# Tractive_System_Active_Light_rev3.net
KiCad netlist of a schematic drawn in EAGLE
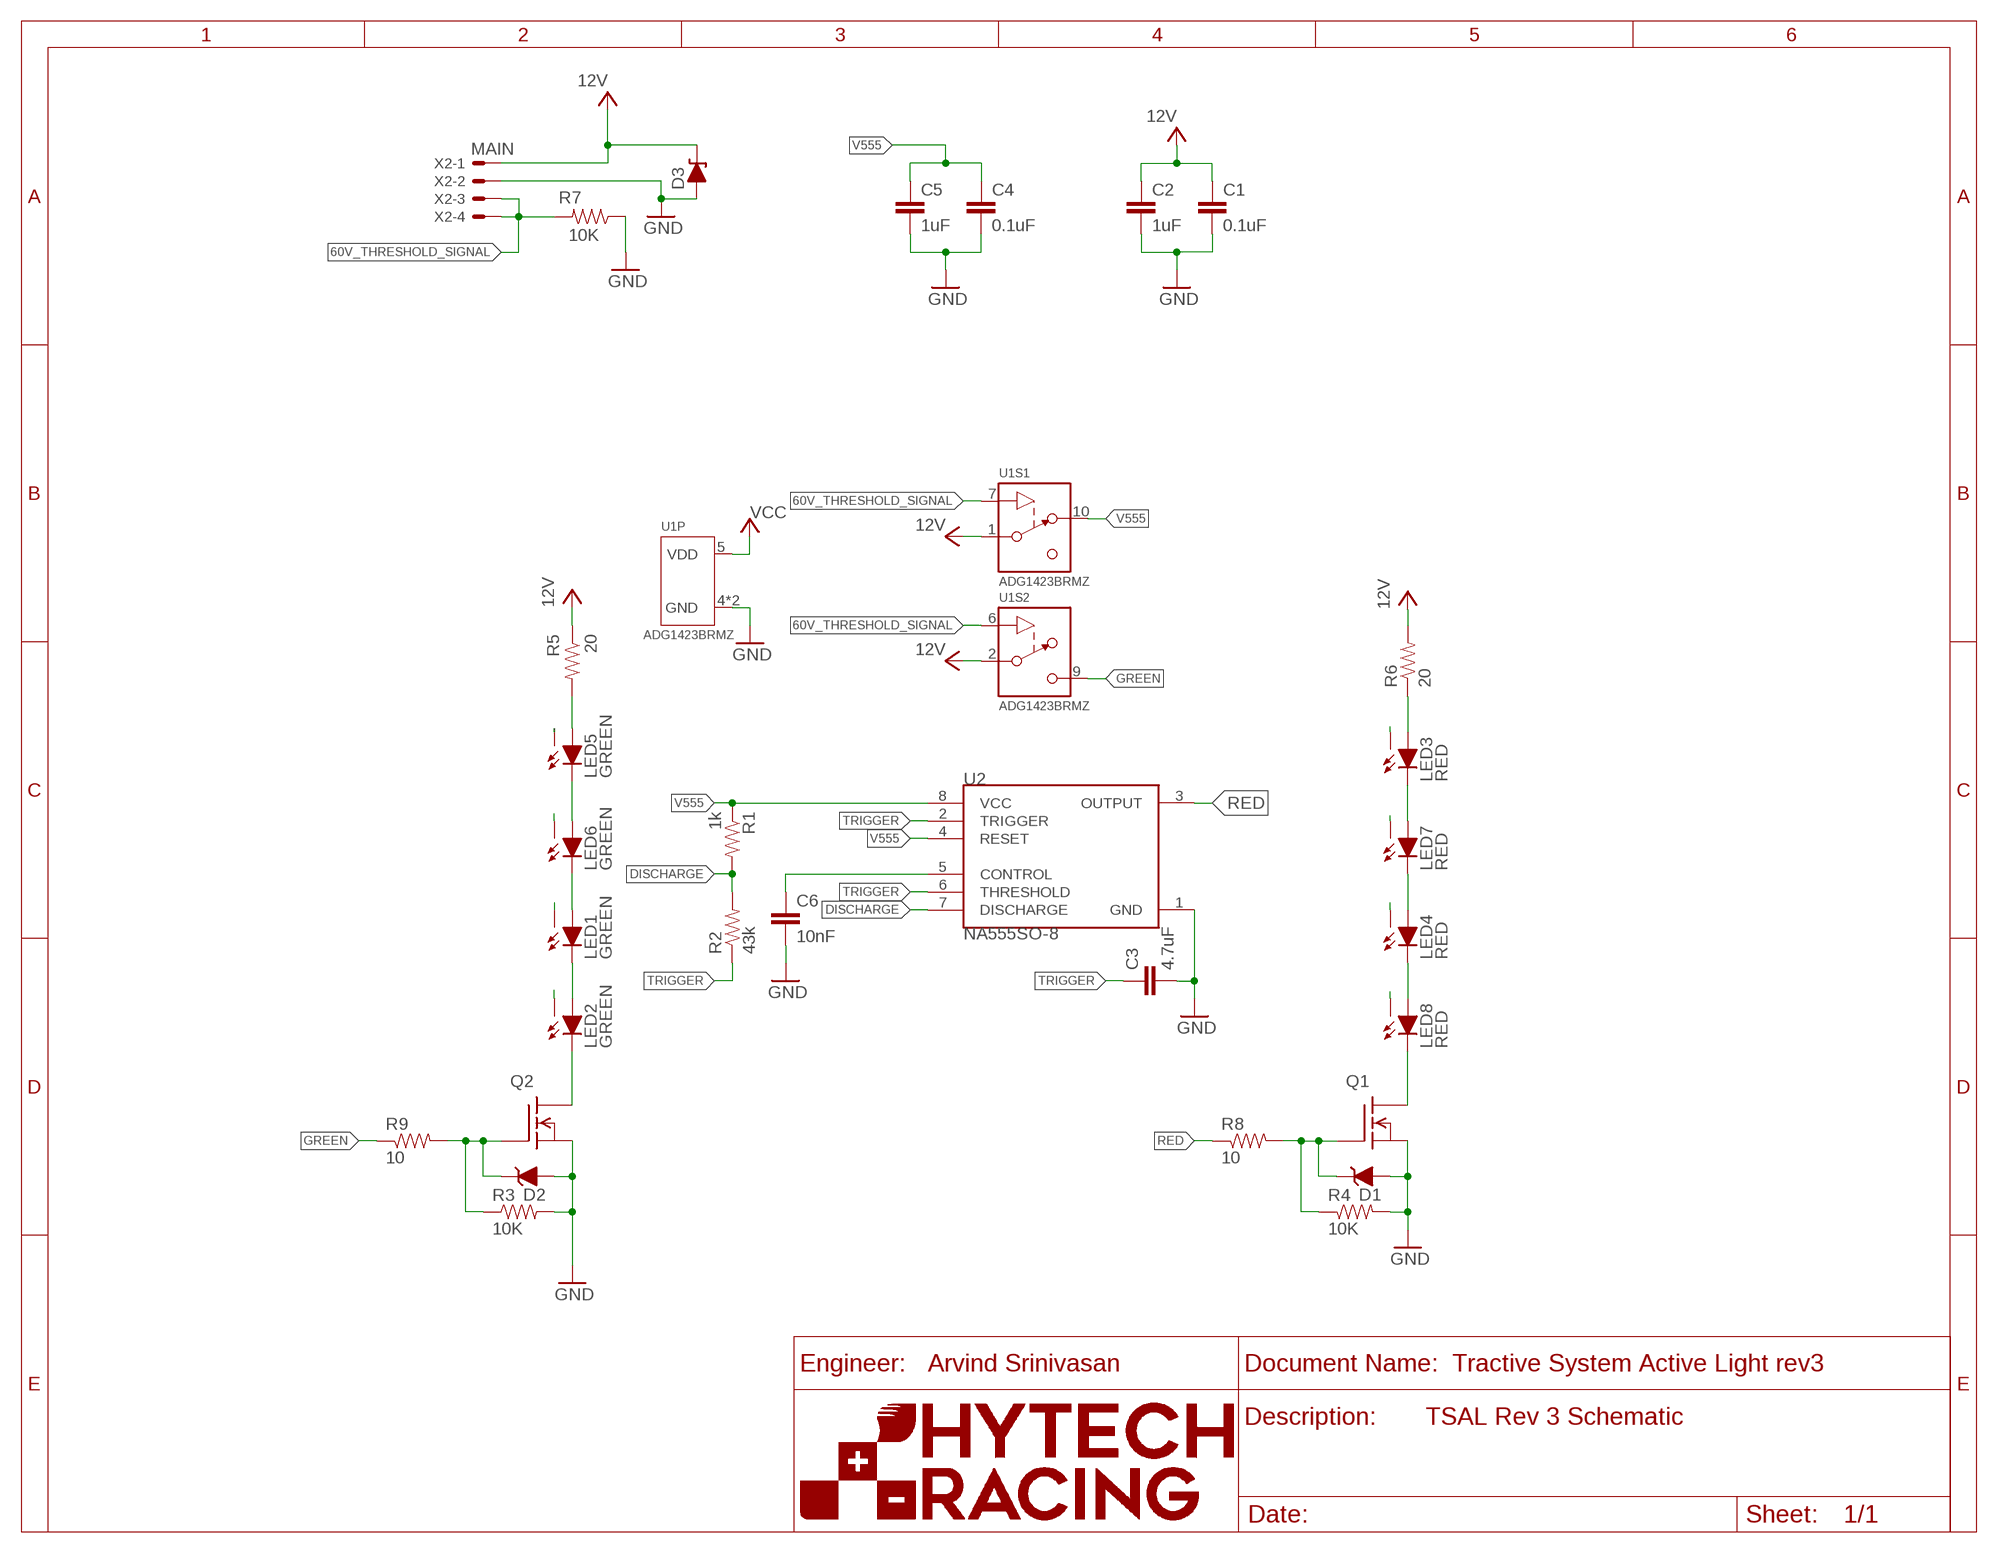
[diagram p0: schematic, sheet 1]

(export (version "E")
  (design (tool "Eeschema 10.0.6"))
  (components
    (comp (ref "C1")
      (value "0.1uF")
      (footprint "eagle-import:0603-CAP")
      (fields (field (name "TOLERANCE") "5%") (field (name "VOLTAGE") "25V"))
      (libsource (lib "eagle-import") (part "CAP0603-CAP"))
    )
    (comp (ref "C2")
      (value "1uF")
      (footprint "eagle-import:0603-CAP")
      (fields (field (name "TOLERANCE") "5%") (field (name "VOLTAGE") "25V"))
      (libsource (lib "eagle-import") (part "CAP0603-CAP"))
    )
    (comp (ref "C3")
      (value "4.7uF")
      (footprint "eagle-import:0603-CAP")
      (fields (field (name "TOLERANCE") "5%") (field (name "VOLTAGE") "25V"))
      (libsource (lib "eagle-import") (part "CAP0603-CAP"))
    )
    (comp (ref "C4")
      (value "0.1uF")
      (footprint "eagle-import:0603-CAP")
      (fields (field (name "TOLERANCE") "5%") (field (name "VOLTAGE") "25V"))
      (libsource (lib "eagle-import") (part "CAP0603-CAP"))
    )
    (comp (ref "C5")
      (value "1uF")
      (footprint "eagle-import:0603-CAP")
      (fields (field (name "TOLERANCE") "5%") (field (name "VOLTAGE") "25V"))
      (libsource (lib "eagle-import") (part "CAP0603-CAP"))
    )
    (comp (ref "C6")
      (value "10nF")
      (footprint "eagle-import:0603-CAP")
      (fields (field (name "TOLERANCE") "5%") (field (name "VOLTAGE") "25V"))
      (libsource (lib "eagle-import") (part "CAP0603-CAP"))
    )
    (comp (ref "D1")
      (value "MMBZ5246BLT1G")
      (footprint "eagle-import:SOT23")
      (libsource (lib "eagle-import") (part "DIODE_ZENER"))
    )
    (comp (ref "D2")
      (value "MMBZ5246BLT1G")
      (footprint "eagle-import:SOT23")
      (libsource (lib "eagle-import") (part "DIODE_ZENER"))
    )
    (comp (ref "D3")
      (value "D15V0S1U2LP1608")
      (footprint "eagle-import:U-DFN1608-2")
      (libsource (lib "eagle-import") (part "TVS_DIODE"))
    )
    (comp (ref "LED1")
      (value "GREEN")
      (footprint "eagle-import:XP-E2")
      (libsource (lib "eagle-import") (part "XP-E2XP-E2"))
    )
    (comp (ref "LED2")
      (value "GREEN")
      (footprint "eagle-import:XP-E2")
      (libsource (lib "eagle-import") (part "XP-E2XP-E2"))
    )
    (comp (ref "LED3")
      (value "RED")
      (footprint "eagle-import:XP-E2")
      (libsource (lib "eagle-import") (part "XP-E2XP-E2"))
    )
    (comp (ref "LED4")
      (value "RED")
      (footprint "eagle-import:XP-E2")
      (libsource (lib "eagle-import") (part "XP-E2XP-E2"))
    )
    (comp (ref "LED5")
      (value "GREEN")
      (footprint "eagle-import:XP-E2")
      (libsource (lib "eagle-import") (part "XP-E2XP-E2"))
    )
    (comp (ref "LED6")
      (value "GREEN")
      (footprint "eagle-import:XP-E2")
      (libsource (lib "eagle-import") (part "XP-E2XP-E2"))
    )
    (comp (ref "LED7")
      (value "RED")
      (footprint "eagle-import:XP-E2")
      (libsource (lib "eagle-import") (part "XP-E2XP-E2"))
    )
    (comp (ref "LED8")
      (value "RED")
      (footprint "eagle-import:XP-E2")
      (libsource (lib "eagle-import") (part "XP-E2XP-E2"))
    )
    (comp (ref "Q1")
      (value "DMG3406LSOT")
      (footprint "eagle-import:SOT23")
      (libsource (lib "eagle-import") (part "DMG3406LSOT"))
    )
    (comp (ref "Q2")
      (value "DMG3406LSOT")
      (footprint "eagle-import:SOT23")
      (libsource (lib "eagle-import") (part "DMG3406LSOT"))
    )
    (comp (ref "R1")
      (value "1k")
      (footprint "eagle-import:0603-RES")
      (fields (field (name "TOLERANCE") "1%"))
      (libsource (lib "eagle-import") (part "RESISTOR0603-RES"))
    )
    (comp (ref "R2")
      (value "43k")
      (footprint "eagle-import:0603-RES")
      (fields (field (name "TOLERANCE") "1%"))
      (libsource (lib "eagle-import") (part "RESISTOR0603-RES"))
    )
    (comp (ref "R3")
      (value "10K")
      (footprint "eagle-import:0603-RES")
      (fields (field (name "TOLERANCE") "1%"))
      (libsource (lib "eagle-import") (part "RESISTOR0603-RES"))
    )
    (comp (ref "R4")
      (value "10K")
      (footprint "eagle-import:0603-RES")
      (fields (field (name "TOLERANCE") "1%"))
      (libsource (lib "eagle-import") (part "RESISTOR0603-RES"))
    )
    (comp (ref "R5")
      (value "20")
      (footprint "eagle-import:0603-RES")
      (fields (field (name "TOLERANCE") "1%"))
      (libsource (lib "eagle-import") (part "RESISTOR0603-RES"))
    )
    (comp (ref "R6")
      (value "20")
      (footprint "eagle-import:0603-RES")
      (fields (field (name "TOLERANCE") "1%"))
      (libsource (lib "eagle-import") (part "RESISTOR0603-RES"))
    )
    (comp (ref "R7")
      (value "10K")
      (footprint "eagle-import:0603-RES")
      (fields (field (name "TOLERANCE") "1%"))
      (libsource (lib "eagle-import") (part "RESISTOR0603-RES"))
    )
    (comp (ref "R8")
      (value "10")
      (footprint "eagle-import:0603-RES")
      (fields (field (name "TOLERANCE") "1%"))
      (libsource (lib "eagle-import") (part "RESISTOR0603-RES"))
    )
    (comp (ref "R9")
      (value "10")
      (footprint "eagle-import:0603-RES")
      (fields (field (name "TOLERANCE") "1%"))
      (libsource (lib "eagle-import") (part "RESISTOR0603-RES"))
    )
    (comp (ref "U1")
      (value "ADG1423")
      (footprint "eagle-import:MSOP-10")
      (fields (field (name "MPN") "ADG1423BRMZ") (field (name "MANUFACTURER") "Analog Devices Inc."))
      (libsource (lib "eagle-import") (part "ADG1423"))
    )
    (comp (ref "U2")
      (value "NA555SO-8")
      (footprint "eagle-import:SOIC-08")
      (libsource (lib "eagle-import") (part "NA555SO-8"))
    )
    (comp (ref "X2")
      (value "MAIN")
      (footprint "eagle-import:NANO-FIT_RIGHT_ANGLE-4-SURFACE")
      (libsource (lib "eagle-import") (part "CONNECTOR-4NANO-FIT_RIGHT_ANGLE-4-SURFACE"))
    )
  )
  (nets
    (net (code "1") (name "/THERM") (class "Default")
      (node (ref "LED1") (pin "X") (pinfunction "X_X") (pintype "passive"))
      (node (ref "LED2") (pin "X") (pinfunction "X_X") (pintype "passive"))
      (node (ref "LED3") (pin "X") (pinfunction "X_X") (pintype "passive"))
      (node (ref "LED4") (pin "X") (pinfunction "X_X") (pintype "passive"))
      (node (ref "LED5") (pin "X") (pinfunction "X_X") (pintype "passive"))
      (node (ref "LED6") (pin "X") (pinfunction "X_X") (pintype "passive"))
      (node (ref "LED7") (pin "X") (pinfunction "X_X") (pintype "passive"))
      (node (ref "LED8") (pin "X") (pinfunction "X_X") (pintype "passive"))
    )
    (net (code "2") (name "12V") (class "Default")
      (node (ref "C1") (pin "1") (pinfunction "1_1") (pintype "passive"))
      (node (ref "C2") (pin "1") (pinfunction "1_1") (pintype "passive"))
      (node (ref "D3") (pin "P$2") (pinfunction "C_P$2") (pintype "passive"))
      (node (ref "R5") (pin "1") (pinfunction "1_1") (pintype "passive"))
      (node (ref "R6") (pin "2") (pinfunction "2_2") (pintype "passive"))
      (node (ref "U1") (pin "1") (pinfunction "S_1") (pintype "bidirectional"))
      (node (ref "U1") (pin "2") (pinfunction "S_2") (pintype "bidirectional"))
      (node (ref "U1") (pin "5") (pinfunction "VDD_5") (pintype "power_in"))
      (node (ref "X2") (pin "1") (pinfunction "S_1") (pintype "passive"))
    )
    (net (code "3") (name "60V_THRESHOLD_SIGNAL") (class "Default")
      (node (ref "R7") (pin "2") (pinfunction "2_2") (pintype "passive"))
      (node (ref "U1") (pin "6") (pinfunction "IN_6") (pintype "input"))
      (node (ref "U1") (pin "7") (pinfunction "IN_7") (pintype "input"))
      (node (ref "X2") (pin "3") (pinfunction "S_3") (pintype "passive"))
      (node (ref "X2") (pin "4") (pinfunction "S_4") (pintype "passive"))
    )
    (net (code "4") (name "DISCHARGE") (class "Default")
      (node (ref "R1") (pin "2") (pinfunction "2_2") (pintype "passive"))
      (node (ref "R2") (pin "2") (pinfunction "2_2") (pintype "passive"))
      (node (ref "U2") (pin "7") (pinfunction "DISCHARGE_7") (pintype "passive"))
    )
    (net (code "5") (name "GND") (class "Default")
      (node (ref "C1") (pin "2") (pinfunction "2_2") (pintype "passive"))
      (node (ref "C2") (pin "2") (pinfunction "2_2") (pintype "passive"))
      (node (ref "C3") (pin "2") (pinfunction "2_2") (pintype "passive"))
      (node (ref "C4") (pin "2") (pinfunction "2_2") (pintype "passive"))
      (node (ref "C5") (pin "2") (pinfunction "2_2") (pintype "passive"))
      (node (ref "C6") (pin "2") (pinfunction "2_2") (pintype "passive"))
      (node (ref "D1") (pin "1") (pinfunction "A_1") (pintype "passive"))
      (node (ref "D2") (pin "1") (pinfunction "A_1") (pintype "passive"))
      (node (ref "D3") (pin "P$1") (pinfunction "A_P$1") (pintype "passive"))
      (node (ref "Q1") (pin "2") (pinfunction "S_2") (pintype "passive"))
      (node (ref "Q2") (pin "2") (pinfunction "S_2") (pintype "passive"))
      (node (ref "R3") (pin "2") (pinfunction "2_2") (pintype "passive"))
      (node (ref "R4") (pin "2") (pinfunction "2_2") (pintype "passive"))
      (node (ref "R7") (pin "1") (pinfunction "1_1") (pintype "passive"))
      (node (ref "U1") (pin "4") (pinfunction "GND_4") (pintype "power_in"))
      (node (ref "U1") (pin "8") (pinfunction "GND_8") (pintype "power_in"))
      (node (ref "U2") (pin "1") (pinfunction "GND_1") (pintype "passive"))
      (node (ref "X2") (pin "2") (pinfunction "S_2") (pintype "passive"))
    )
    (net (code "6") (name "GREEN") (class "Default")
      (node (ref "R9") (pin "1") (pinfunction "1_1") (pintype "passive"))
      (node (ref "U1") (pin "9") (pinfunction "D_9") (pintype "bidirectional"))
    )
    (net (code "7") (name "Net-(D1-C)") (class "Default")
      (node (ref "D1") (pin "3") (pinfunction "C_3") (pintype "passive"))
      (node (ref "Q1") (pin "1") (pinfunction "G_1") (pintype "passive"))
      (node (ref "R4") (pin "1") (pinfunction "1_1") (pintype "passive"))
      (node (ref "R8") (pin "2") (pinfunction "2_2") (pintype "passive"))
    )
    (net (code "8") (name "Net-(D2-C)") (class "Default")
      (node (ref "D2") (pin "3") (pinfunction "C_3") (pintype "passive"))
      (node (ref "Q2") (pin "1") (pinfunction "G_1") (pintype "passive"))
      (node (ref "R3") (pin "1") (pinfunction "1_1") (pintype "passive"))
      (node (ref "R9") (pin "2") (pinfunction "2_2") (pintype "passive"))
    )
    (net (code "9") (name "Net-(LED1-PadA)") (class "Default")
      (node (ref "LED1") (pin "A") (pinfunction "A_A") (pintype "passive"))
      (node (ref "LED6") (pin "C") (pinfunction "C_C") (pintype "passive"))
    )
    (net (code "10") (name "Net-(LED1-PadC)") (class "Default")
      (node (ref "LED1") (pin "C") (pinfunction "C_C") (pintype "passive"))
      (node (ref "LED2") (pin "A") (pinfunction "A_A") (pintype "passive"))
    )
    (net (code "11") (name "Net-(LED3-PadA)") (class "Default")
      (node (ref "LED3") (pin "A") (pinfunction "A_A") (pintype "passive"))
      (node (ref "R6") (pin "1") (pinfunction "1_1") (pintype "passive"))
    )
    (net (code "12") (name "Net-(LED3-PadC)") (class "Default")
      (node (ref "LED3") (pin "C") (pinfunction "C_C") (pintype "passive"))
      (node (ref "LED7") (pin "A") (pinfunction "A_A") (pintype "passive"))
    )
    (net (code "13") (name "Net-(LED4-PadA)") (class "Default")
      (node (ref "LED4") (pin "A") (pinfunction "A_A") (pintype "passive"))
      (node (ref "LED7") (pin "C") (pinfunction "C_C") (pintype "passive"))
    )
    (net (code "14") (name "Net-(LED4-PadC)") (class "Default")
      (node (ref "LED4") (pin "C") (pinfunction "C_C") (pintype "passive"))
      (node (ref "LED8") (pin "A") (pinfunction "A_A") (pintype "passive"))
    )
    (net (code "15") (name "Net-(LED5-PadA)") (class "Default")
      (node (ref "LED5") (pin "A") (pinfunction "A_A") (pintype "passive"))
      (node (ref "R5") (pin "2") (pinfunction "2_2") (pintype "passive"))
    )
    (net (code "16") (name "Net-(LED5-PadC)") (class "Default")
      (node (ref "LED5") (pin "C") (pinfunction "C_C") (pintype "passive"))
      (node (ref "LED6") (pin "A") (pinfunction "A_A") (pintype "passive"))
    )
    (net (code "17") (name "Net-(Q1-D)") (class "Default")
      (node (ref "LED8") (pin "C") (pinfunction "C_C") (pintype "passive"))
      (node (ref "Q1") (pin "3") (pinfunction "D_3") (pintype "passive"))
    )
    (net (code "18") (name "Net-(Q2-D)") (class "Default")
      (node (ref "LED2") (pin "C") (pinfunction "C_C") (pintype "passive"))
      (node (ref "Q2") (pin "3") (pinfunction "D_3") (pintype "passive"))
    )
    (net (code "19") (name "Net-(U2-CONTROL)") (class "Default")
      (node (ref "C6") (pin "1") (pinfunction "1_1") (pintype "passive"))
      (node (ref "U2") (pin "5") (pinfunction "CONTROL_5") (pintype "passive"))
    )
    (net (code "20") (name "RED") (class "Default")
      (node (ref "R8") (pin "1") (pinfunction "1_1") (pintype "passive"))
      (node (ref "U2") (pin "3") (pinfunction "OUTPUT_3") (pintype "passive"))
    )
    (net (code "21") (name "TRIGGER") (class "Default")
      (node (ref "C3") (pin "1") (pinfunction "1_1") (pintype "passive"))
      (node (ref "R2") (pin "1") (pinfunction "1_1") (pintype "passive"))
      (node (ref "U2") (pin "2") (pinfunction "TRIGGER_2") (pintype "passive"))
      (node (ref "U2") (pin "6") (pinfunction "THRESHOLD_6") (pintype "passive"))
    )
    (net (code "22") (name "V555") (class "Default")
      (node (ref "C4") (pin "1") (pinfunction "1_1") (pintype "passive"))
      (node (ref "C5") (pin "1") (pinfunction "1_1") (pintype "passive"))
      (node (ref "R1") (pin "1") (pinfunction "1_1") (pintype "passive"))
      (node (ref "U1") (pin "10") (pinfunction "D_10") (pintype "bidirectional"))
      (node (ref "U2") (pin "4") (pinfunction "RESET_4") (pintype "passive"))
      (node (ref "U2") (pin "8") (pinfunction "VCC_8") (pintype "passive"))
    )
  )
)
